# D_OUTPUT.net
KiCad netlist of a schematic drawn in Altium Designer
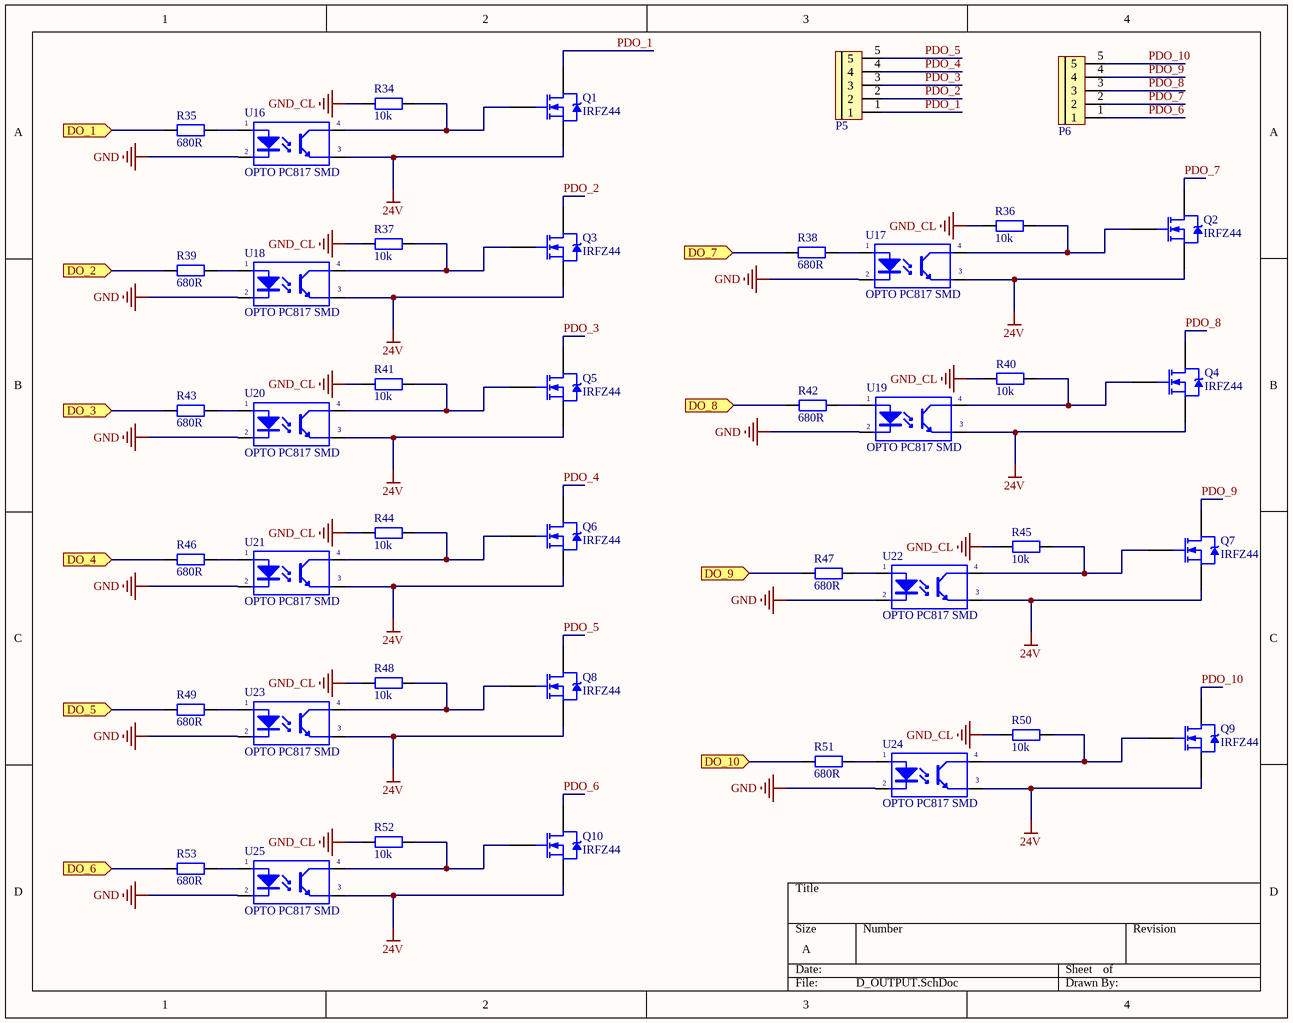
[diagram p0: D_OUTPUT.SchDoc]

(export (version "E")
  (design (tool "Eeschema 10.0.6"))
  (components
    (comp (ref "P5")
      (value "CON 5 EDG5.08")
      (footprint "CON 5 5EDG5.08")
      (description "Cắm")
      (libsource (lib "Altium_Lib_by_KhueNguyenCreator") (part "CON 5 EDG5.08"))
    )
    (comp (ref "P6")
      (value "CON 5 EDG5.08")
      (footprint "CON 5 5EDG5.08")
      (description "Cắm")
      (libsource (lib "Altium_Lib_by_KhueNguyenCreator") (part "CON 5 EDG5.08"))
    )
    (comp (ref "Q1")
      (value "IRFZ44")
      (footprint "TO220")
      (description "N-Channel Power MOSFET")
      (libsource (lib "Altium_Lib_by_KhueNguyenCreator") (part "IRFZ44 DIP"))
    )
    (comp (ref "Q2")
      (value "IRFZ44")
      (footprint "TO220")
      (description "N-Channel Power MOSFET")
      (libsource (lib "Altium_Lib_by_KhueNguyenCreator") (part "IRFZ44 DIP"))
    )
    (comp (ref "Q3")
      (value "IRFZ44")
      (footprint "TO220")
      (description "N-Channel Power MOSFET")
      (libsource (lib "Altium_Lib_by_KhueNguyenCreator") (part "IRFZ44 DIP"))
    )
    (comp (ref "Q4")
      (value "IRFZ44")
      (footprint "TO220")
      (description "N-Channel Power MOSFET")
      (libsource (lib "Altium_Lib_by_KhueNguyenCreator") (part "IRFZ44 DIP"))
    )
    (comp (ref "Q5")
      (value "IRFZ44")
      (footprint "TO220")
      (description "N-Channel Power MOSFET")
      (libsource (lib "Altium_Lib_by_KhueNguyenCreator") (part "IRFZ44 DIP"))
    )
    (comp (ref "Q6")
      (value "IRFZ44")
      (footprint "TO220")
      (description "N-Channel Power MOSFET")
      (libsource (lib "Altium_Lib_by_KhueNguyenCreator") (part "IRFZ44 DIP"))
    )
    (comp (ref "Q7")
      (value "IRFZ44")
      (footprint "TO220")
      (description "N-Channel Power MOSFET")
      (libsource (lib "Altium_Lib_by_KhueNguyenCreator") (part "IRFZ44 DIP"))
    )
    (comp (ref "Q8")
      (value "IRFZ44")
      (footprint "TO220")
      (description "N-Channel Power MOSFET")
      (libsource (lib "Altium_Lib_by_KhueNguyenCreator") (part "IRFZ44 DIP"))
    )
    (comp (ref "Q9")
      (value "IRFZ44")
      (footprint "TO220")
      (description "N-Channel Power MOSFET")
      (libsource (lib "Altium_Lib_by_KhueNguyenCreator") (part "IRFZ44 DIP"))
    )
    (comp (ref "Q10")
      (value "IRFZ44")
      (footprint "TO220")
      (description "N-Channel Power MOSFET")
      (libsource (lib "Altium_Lib_by_KhueNguyenCreator") (part "IRFZ44 DIP"))
    )
    (comp (ref "R34")
      (value "10k")
      (footprint "tro smd 0805")
      (description "Dán")
      (libsource (lib "Altium_Lib_by_KhueNguyenCreator") (part "Tro 0805 5% 10k"))
    )
    (comp (ref "R35")
      (value "680R")
      (footprint "Tro SMD 0805")
      (description "Dán")
      (libsource (lib "Altium_Lib_by_KhueNguyenCreator") (part "Tro 0805 5% 680R"))
    )
    (comp (ref "R36")
      (value "10k")
      (footprint "tro smd 0805")
      (description "Dán")
      (libsource (lib "Altium_Lib_by_KhueNguyenCreator") (part "Tro 0805 5% 10k"))
    )
    (comp (ref "R37")
      (value "10k")
      (footprint "tro smd 0805")
      (description "Dán")
      (libsource (lib "Altium_Lib_by_KhueNguyenCreator") (part "Tro 0805 5% 10k"))
    )
    (comp (ref "R38")
      (value "680R")
      (footprint "Tro SMD 0805")
      (description "Dán")
      (libsource (lib "Altium_Lib_by_KhueNguyenCreator") (part "Tro 0805 5% 680R"))
    )
    (comp (ref "R39")
      (value "680R")
      (footprint "Tro SMD 0805")
      (description "Dán")
      (libsource (lib "Altium_Lib_by_KhueNguyenCreator") (part "Tro 0805 5% 680R"))
    )
    (comp (ref "R40")
      (value "10k")
      (footprint "tro smd 0805")
      (description "Dán")
      (libsource (lib "Altium_Lib_by_KhueNguyenCreator") (part "Tro 0805 5% 10k"))
    )
    (comp (ref "R41")
      (value "10k")
      (footprint "tro smd 0805")
      (description "Dán")
      (libsource (lib "Altium_Lib_by_KhueNguyenCreator") (part "Tro 0805 5% 10k"))
    )
    (comp (ref "R42")
      (value "680R")
      (footprint "Tro SMD 0805")
      (description "Dán")
      (libsource (lib "Altium_Lib_by_KhueNguyenCreator") (part "Tro 0805 5% 680R"))
    )
    (comp (ref "R43")
      (value "680R")
      (footprint "Tro SMD 0805")
      (description "Dán")
      (libsource (lib "Altium_Lib_by_KhueNguyenCreator") (part "Tro 0805 5% 680R"))
    )
    (comp (ref "R44")
      (value "10k")
      (footprint "tro smd 0805")
      (description "Dán")
      (libsource (lib "Altium_Lib_by_KhueNguyenCreator") (part "Tro 0805 5% 10k"))
    )
    (comp (ref "R45")
      (value "10k")
      (footprint "tro smd 0805")
      (description "Dán")
      (libsource (lib "Altium_Lib_by_KhueNguyenCreator") (part "Tro 0805 5% 10k"))
    )
    (comp (ref "R46")
      (value "680R")
      (footprint "Tro SMD 0805")
      (description "Dán")
      (libsource (lib "Altium_Lib_by_KhueNguyenCreator") (part "Tro 0805 5% 680R"))
    )
    (comp (ref "R47")
      (value "680R")
      (footprint "Tro SMD 0805")
      (description "Dán")
      (libsource (lib "Altium_Lib_by_KhueNguyenCreator") (part "Tro 0805 5% 680R"))
    )
    (comp (ref "R48")
      (value "10k")
      (footprint "tro smd 0805")
      (description "Dán")
      (libsource (lib "Altium_Lib_by_KhueNguyenCreator") (part "Tro 0805 5% 10k"))
    )
    (comp (ref "R49")
      (value "680R")
      (footprint "Tro SMD 0805")
      (description "Dán")
      (libsource (lib "Altium_Lib_by_KhueNguyenCreator") (part "Tro 0805 5% 680R"))
    )
    (comp (ref "R50")
      (value "10k")
      (footprint "tro smd 0805")
      (description "Dán")
      (libsource (lib "Altium_Lib_by_KhueNguyenCreator") (part "Tro 0805 5% 10k"))
    )
    (comp (ref "R51")
      (value "680R")
      (footprint "Tro SMD 0805")
      (description "Dán")
      (libsource (lib "Altium_Lib_by_KhueNguyenCreator") (part "Tro 0805 5% 680R"))
    )
    (comp (ref "R52")
      (value "10k")
      (footprint "tro smd 0805")
      (description "Dán")
      (libsource (lib "Altium_Lib_by_KhueNguyenCreator") (part "Tro 0805 5% 10k"))
    )
    (comp (ref "R53")
      (value "680R")
      (footprint "Tro SMD 0805")
      (description "Dán")
      (libsource (lib "Altium_Lib_by_KhueNguyenCreator") (part "Tro 0805 5% 680R"))
    )
    (comp (ref "U16")
      (value "OPTO PC817 SMD")
      (footprint "SOP4")
      (description "Single Opto")
      (libsource (lib "Altium_Lib_by_KhueNguyenCreator") (part "OPTO PC817 SMD"))
    )
    (comp (ref "U17")
      (value "OPTO PC817 SMD")
      (footprint "SOP4")
      (description "Single Opto")
      (libsource (lib "Altium_Lib_by_KhueNguyenCreator") (part "OPTO PC817 SMD"))
    )
    (comp (ref "U18")
      (value "OPTO PC817 SMD")
      (footprint "SOP4")
      (description "Single Opto")
      (libsource (lib "Altium_Lib_by_KhueNguyenCreator") (part "OPTO PC817 SMD"))
    )
    (comp (ref "U19")
      (value "OPTO PC817 SMD")
      (footprint "SOP4")
      (description "Single Opto")
      (libsource (lib "Altium_Lib_by_KhueNguyenCreator") (part "OPTO PC817 SMD"))
    )
    (comp (ref "U20")
      (value "OPTO PC817 SMD")
      (footprint "SOP4")
      (description "Single Opto")
      (libsource (lib "Altium_Lib_by_KhueNguyenCreator") (part "OPTO PC817 SMD"))
    )
    (comp (ref "U21")
      (value "OPTO PC817 SMD")
      (footprint "SOP4")
      (description "Single Opto")
      (libsource (lib "Altium_Lib_by_KhueNguyenCreator") (part "OPTO PC817 SMD"))
    )
    (comp (ref "U22")
      (value "OPTO PC817 SMD")
      (footprint "SOP4")
      (description "Single Opto")
      (libsource (lib "Altium_Lib_by_KhueNguyenCreator") (part "OPTO PC817 SMD"))
    )
    (comp (ref "U23")
      (value "OPTO PC817 SMD")
      (footprint "SOP4")
      (description "Single Opto")
      (libsource (lib "Altium_Lib_by_KhueNguyenCreator") (part "OPTO PC817 SMD"))
    )
    (comp (ref "U24")
      (value "OPTO PC817 SMD")
      (footprint "SOP4")
      (description "Single Opto")
      (libsource (lib "Altium_Lib_by_KhueNguyenCreator") (part "OPTO PC817 SMD"))
    )
    (comp (ref "U25")
      (value "OPTO PC817 SMD")
      (footprint "SOP4")
      (description "Single Opto")
      (libsource (lib "Altium_Lib_by_KhueNguyenCreator") (part "OPTO PC817 SMD"))
    )
  )
  (nets
    (net (code "1") (name "/DO_1") (class "Default")
      (node (ref "R35") (pin "1") (pinfunction "1_1") (pintype "passive"))
    )
    (net (code "2") (name "/DO_2") (class "Default")
      (node (ref "R39") (pin "1") (pinfunction "1_1") (pintype "passive"))
    )
    (net (code "3") (name "/DO_3") (class "Default")
      (node (ref "R43") (pin "1") (pinfunction "1_1") (pintype "passive"))
    )
    (net (code "4") (name "/DO_4") (class "Default")
      (node (ref "R46") (pin "1") (pinfunction "1_1") (pintype "passive"))
    )
    (net (code "5") (name "/DO_5") (class "Default")
      (node (ref "R49") (pin "1") (pinfunction "1_1") (pintype "passive"))
    )
    (net (code "6") (name "/DO_6") (class "Default")
      (node (ref "R53") (pin "1") (pinfunction "1_1") (pintype "passive"))
    )
    (net (code "7") (name "/DO_7") (class "Default")
      (node (ref "R38") (pin "1") (pinfunction "1_1") (pintype "passive"))
    )
    (net (code "8") (name "/DO_8") (class "Default")
      (node (ref "R42") (pin "1") (pinfunction "1_1") (pintype "passive"))
    )
    (net (code "9") (name "/DO_9") (class "Default")
      (node (ref "R47") (pin "1") (pinfunction "1_1") (pintype "passive"))
    )
    (net (code "10") (name "/DO_10") (class "Default")
      (node (ref "R51") (pin "1") (pinfunction "1_1") (pintype "passive"))
    )
    (net (code "11") (name "/PDO_1") (class "Default")
      (node (ref "P5") (pin "1") (pinfunction "1_1") (pintype "passive"))
      (node (ref "Q1") (pin "2") (pinfunction "D_2") (pintype "passive"))
    )
    (net (code "12") (name "/PDO_2") (class "Default")
      (node (ref "P5") (pin "2") (pinfunction "2_2") (pintype "passive"))
      (node (ref "Q3") (pin "2") (pinfunction "D_2") (pintype "passive"))
    )
    (net (code "13") (name "/PDO_3") (class "Default")
      (node (ref "P5") (pin "3") (pinfunction "3_3") (pintype "passive"))
      (node (ref "Q5") (pin "2") (pinfunction "D_2") (pintype "passive"))
    )
    (net (code "14") (name "/PDO_4") (class "Default")
      (node (ref "P5") (pin "4") (pinfunction "4_4") (pintype "passive"))
      (node (ref "Q6") (pin "2") (pinfunction "D_2") (pintype "passive"))
    )
    (net (code "15") (name "/PDO_5") (class "Default")
      (node (ref "P5") (pin "5") (pinfunction "5_5") (pintype "passive"))
      (node (ref "Q8") (pin "2") (pinfunction "D_2") (pintype "passive"))
    )
    (net (code "16") (name "/PDO_6") (class "Default")
      (node (ref "P6") (pin "1") (pinfunction "1_1") (pintype "passive"))
      (node (ref "Q10") (pin "2") (pinfunction "D_2") (pintype "passive"))
    )
    (net (code "17") (name "/PDO_7") (class "Default")
      (node (ref "P6") (pin "2") (pinfunction "2_2") (pintype "passive"))
      (node (ref "Q2") (pin "2") (pinfunction "D_2") (pintype "passive"))
    )
    (net (code "18") (name "/PDO_8") (class "Default")
      (node (ref "P6") (pin "3") (pinfunction "3_3") (pintype "passive"))
      (node (ref "Q4") (pin "2") (pinfunction "D_2") (pintype "passive"))
    )
    (net (code "19") (name "/PDO_9") (class "Default")
      (node (ref "P6") (pin "4") (pinfunction "4_4") (pintype "passive"))
      (node (ref "Q7") (pin "2") (pinfunction "D_2") (pintype "passive"))
    )
    (net (code "20") (name "/PDO_10") (class "Default")
      (node (ref "P6") (pin "5") (pinfunction "5_5") (pintype "passive"))
      (node (ref "Q9") (pin "2") (pinfunction "D_2") (pintype "passive"))
    )
    (net (code "21") (name "24V") (class "Default")
      (node (ref "Q1") (pin "3") (pinfunction "S_3") (pintype "passive"))
      (node (ref "Q10") (pin "3") (pinfunction "S_3") (pintype "passive"))
      (node (ref "Q2") (pin "3") (pinfunction "S_3") (pintype "passive"))
      (node (ref "Q3") (pin "3") (pinfunction "S_3") (pintype "passive"))
      (node (ref "Q4") (pin "3") (pinfunction "S_3") (pintype "passive"))
      (node (ref "Q5") (pin "3") (pinfunction "S_3") (pintype "passive"))
      (node (ref "Q6") (pin "3") (pinfunction "S_3") (pintype "passive"))
      (node (ref "Q7") (pin "3") (pinfunction "S_3") (pintype "passive"))
      (node (ref "Q8") (pin "3") (pinfunction "S_3") (pintype "passive"))
      (node (ref "Q9") (pin "3") (pinfunction "S_3") (pintype "passive"))
      (node (ref "U16") (pin "3") (pinfunction "E_3") (pintype "passive"))
      (node (ref "U17") (pin "3") (pinfunction "E_3") (pintype "passive"))
      (node (ref "U18") (pin "3") (pinfunction "E_3") (pintype "passive"))
      (node (ref "U19") (pin "3") (pinfunction "E_3") (pintype "passive"))
      (node (ref "U20") (pin "3") (pinfunction "E_3") (pintype "passive"))
      (node (ref "U21") (pin "3") (pinfunction "E_3") (pintype "passive"))
      (node (ref "U22") (pin "3") (pinfunction "E_3") (pintype "passive"))
      (node (ref "U23") (pin "3") (pinfunction "E_3") (pintype "passive"))
      (node (ref "U24") (pin "3") (pinfunction "E_3") (pintype "passive"))
      (node (ref "U25") (pin "3") (pinfunction "E_3") (pintype "passive"))
    )
    (net (code "22") (name "GND") (class "Default")
      (node (ref "U16") (pin "2") (pinfunction "K_2") (pintype "passive"))
      (node (ref "U17") (pin "2") (pinfunction "K_2") (pintype "passive"))
      (node (ref "U18") (pin "2") (pinfunction "K_2") (pintype "passive"))
      (node (ref "U19") (pin "2") (pinfunction "K_2") (pintype "passive"))
      (node (ref "U20") (pin "2") (pinfunction "K_2") (pintype "passive"))
      (node (ref "U21") (pin "2") (pinfunction "K_2") (pintype "passive"))
      (node (ref "U22") (pin "2") (pinfunction "K_2") (pintype "passive"))
      (node (ref "U23") (pin "2") (pinfunction "K_2") (pintype "passive"))
      (node (ref "U24") (pin "2") (pinfunction "K_2") (pintype "passive"))
      (node (ref "U25") (pin "2") (pinfunction "K_2") (pintype "passive"))
    )
    (net (code "23") (name "GND_CL") (class "Default")
      (node (ref "R34") (pin "1") (pinfunction "1_1") (pintype "passive"))
      (node (ref "R36") (pin "1") (pinfunction "1_1") (pintype "passive"))
      (node (ref "R37") (pin "1") (pinfunction "1_1") (pintype "passive"))
      (node (ref "R40") (pin "1") (pinfunction "1_1") (pintype "passive"))
      (node (ref "R41") (pin "1") (pinfunction "1_1") (pintype "passive"))
      (node (ref "R44") (pin "1") (pinfunction "1_1") (pintype "passive"))
      (node (ref "R45") (pin "1") (pinfunction "1_1") (pintype "passive"))
      (node (ref "R48") (pin "1") (pinfunction "1_1") (pintype "passive"))
      (node (ref "R50") (pin "1") (pinfunction "1_1") (pintype "passive"))
      (node (ref "R52") (pin "1") (pinfunction "1_1") (pintype "passive"))
    )
    (net (code "24") (name "Net-(Q1-G)") (class "Default")
      (node (ref "Q1") (pin "1") (pinfunction "G_1") (pintype "passive"))
      (node (ref "R34") (pin "2") (pinfunction "2_2") (pintype "passive"))
      (node (ref "U16") (pin "4") (pinfunction "C_4") (pintype "passive"))
    )
    (net (code "25") (name "Net-(Q2-G)") (class "Default")
      (node (ref "Q2") (pin "1") (pinfunction "G_1") (pintype "passive"))
      (node (ref "R36") (pin "2") (pinfunction "2_2") (pintype "passive"))
      (node (ref "U17") (pin "4") (pinfunction "C_4") (pintype "passive"))
    )
    (net (code "26") (name "Net-(Q3-G)") (class "Default")
      (node (ref "Q3") (pin "1") (pinfunction "G_1") (pintype "passive"))
      (node (ref "R37") (pin "2") (pinfunction "2_2") (pintype "passive"))
      (node (ref "U18") (pin "4") (pinfunction "C_4") (pintype "passive"))
    )
    (net (code "27") (name "Net-(Q4-G)") (class "Default")
      (node (ref "Q4") (pin "1") (pinfunction "G_1") (pintype "passive"))
      (node (ref "R40") (pin "2") (pinfunction "2_2") (pintype "passive"))
      (node (ref "U19") (pin "4") (pinfunction "C_4") (pintype "passive"))
    )
    (net (code "28") (name "Net-(Q5-G)") (class "Default")
      (node (ref "Q5") (pin "1") (pinfunction "G_1") (pintype "passive"))
      (node (ref "R41") (pin "2") (pinfunction "2_2") (pintype "passive"))
      (node (ref "U20") (pin "4") (pinfunction "C_4") (pintype "passive"))
    )
    (net (code "29") (name "Net-(Q6-G)") (class "Default")
      (node (ref "Q6") (pin "1") (pinfunction "G_1") (pintype "passive"))
      (node (ref "R44") (pin "2") (pinfunction "2_2") (pintype "passive"))
      (node (ref "U21") (pin "4") (pinfunction "C_4") (pintype "passive"))
    )
    (net (code "30") (name "Net-(Q7-G)") (class "Default")
      (node (ref "Q7") (pin "1") (pinfunction "G_1") (pintype "passive"))
      (node (ref "R45") (pin "2") (pinfunction "2_2") (pintype "passive"))
      (node (ref "U22") (pin "4") (pinfunction "C_4") (pintype "passive"))
    )
    (net (code "31") (name "Net-(Q8-G)") (class "Default")
      (node (ref "Q8") (pin "1") (pinfunction "G_1") (pintype "passive"))
      (node (ref "R48") (pin "2") (pinfunction "2_2") (pintype "passive"))
      (node (ref "U23") (pin "4") (pinfunction "C_4") (pintype "passive"))
    )
    (net (code "32") (name "Net-(Q9-G)") (class "Default")
      (node (ref "Q9") (pin "1") (pinfunction "G_1") (pintype "passive"))
      (node (ref "R50") (pin "2") (pinfunction "2_2") (pintype "passive"))
      (node (ref "U24") (pin "4") (pinfunction "C_4") (pintype "passive"))
    )
    (net (code "33") (name "Net-(Q10-G)") (class "Default")
      (node (ref "Q10") (pin "1") (pinfunction "G_1") (pintype "passive"))
      (node (ref "R52") (pin "2") (pinfunction "2_2") (pintype "passive"))
      (node (ref "U25") (pin "4") (pinfunction "C_4") (pintype "passive"))
    )
    (net (code "34") (name "Net-(U16-A)") (class "Default")
      (node (ref "R35") (pin "2") (pinfunction "2_2") (pintype "passive"))
      (node (ref "U16") (pin "1") (pinfunction "A_1") (pintype "passive"))
    )
    (net (code "35") (name "Net-(U17-A)") (class "Default")
      (node (ref "R38") (pin "2") (pinfunction "2_2") (pintype "passive"))
      (node (ref "U17") (pin "1") (pinfunction "A_1") (pintype "passive"))
    )
    (net (code "36") (name "Net-(U18-A)") (class "Default")
      (node (ref "R39") (pin "2") (pinfunction "2_2") (pintype "passive"))
      (node (ref "U18") (pin "1") (pinfunction "A_1") (pintype "passive"))
    )
    (net (code "37") (name "Net-(U19-A)") (class "Default")
      (node (ref "R42") (pin "2") (pinfunction "2_2") (pintype "passive"))
      (node (ref "U19") (pin "1") (pinfunction "A_1") (pintype "passive"))
    )
    (net (code "38") (name "Net-(U20-A)") (class "Default")
      (node (ref "R43") (pin "2") (pinfunction "2_2") (pintype "passive"))
      (node (ref "U20") (pin "1") (pinfunction "A_1") (pintype "passive"))
    )
    (net (code "39") (name "Net-(U21-A)") (class "Default")
      (node (ref "R46") (pin "2") (pinfunction "2_2") (pintype "passive"))
      (node (ref "U21") (pin "1") (pinfunction "A_1") (pintype "passive"))
    )
    (net (code "40") (name "Net-(U22-A)") (class "Default")
      (node (ref "R47") (pin "2") (pinfunction "2_2") (pintype "passive"))
      (node (ref "U22") (pin "1") (pinfunction "A_1") (pintype "passive"))
    )
    (net (code "41") (name "Net-(U23-A)") (class "Default")
      (node (ref "R49") (pin "2") (pinfunction "2_2") (pintype "passive"))
      (node (ref "U23") (pin "1") (pinfunction "A_1") (pintype "passive"))
    )
    (net (code "42") (name "Net-(U24-A)") (class "Default")
      (node (ref "R51") (pin "2") (pinfunction "2_2") (pintype "passive"))
      (node (ref "U24") (pin "1") (pinfunction "A_1") (pintype "passive"))
    )
    (net (code "43") (name "Net-(U25-A)") (class "Default")
      (node (ref "R53") (pin "2") (pinfunction "2_2") (pintype "passive"))
      (node (ref "U25") (pin "1") (pinfunction "A_1") (pintype "passive"))
    )
  )
)
